# 5-PMU.net
KiCad netlist of a schematic drawn in Altium Designer
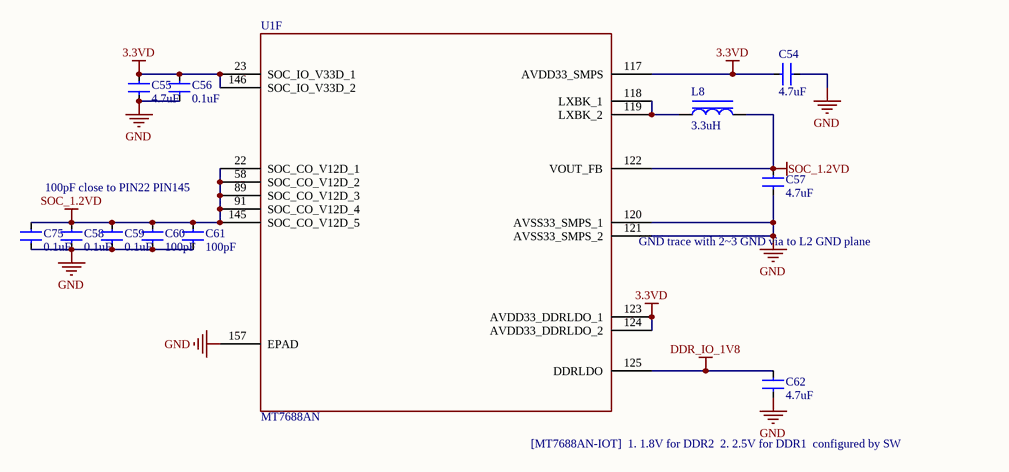
[diagram p0: 5-PMU.SchDoc]

(export (version "E")
  (design (tool "Eeschema 10.0.6"))
  (components
    (comp (ref "C54")
      (value "4.7uF")
      (footprint "C0402")
      (description "普通小电容")
      (libsource (lib "LIB_MANGO") (part "CAP"))
    )
    (comp (ref "C55")
      (value "4.7uF")
      (footprint "C0402")
      (description "普通小电容")
      (libsource (lib "LIB_MANGO") (part "CAP"))
    )
    (comp (ref "C56")
      (value "0.1uF")
      (footprint "C0402")
      (description "普通小电容")
      (libsource (lib "LIB_MANGO") (part "CAP"))
    )
    (comp (ref "C57")
      (value "4.7uF")
      (footprint "C0402")
      (description "普通小电容")
      (libsource (lib "LIB_MANGO") (part "CAP"))
    )
    (comp (ref "C58")
      (value "0.1uF")
      (footprint "C0402")
      (description "普通小电容")
      (libsource (lib "LIB_MANGO") (part "CAP"))
    )
    (comp (ref "C59")
      (value "0.1uF")
      (footprint "C0402")
      (description "普通小电容")
      (libsource (lib "LIB_MANGO") (part "CAP"))
    )
    (comp (ref "C60")
      (value "100pF")
      (footprint "C0402")
      (description "普通小电容")
      (libsource (lib "LIB_MANGO") (part "CAP"))
    )
    (comp (ref "C61")
      (value "100pF")
      (footprint "C0402")
      (description "普通小电容")
      (libsource (lib "LIB_MANGO") (part "CAP"))
    )
    (comp (ref "C62")
      (value "4.7uF")
      (footprint "C0402")
      (description "普通小电容")
      (libsource (lib "LIB_MANGO") (part "CAP"))
    )
    (comp (ref "C75")
      (value "0.1uF")
      (footprint "C0402")
      (description "普通小电容")
      (libsource (lib "LIB_MANGO") (part "CAP"))
    )
    (comp (ref "L8")
      (value "3.3uH")
      (footprint "VLS3012E")
      (description "vls3012小电感")
      (libsource (lib "LIB_MANGO") (part "L"))
    )
    (comp (ref "U1")
      (value "MT7688AN")
      (footprint "MT7628AN/DRQFN156/SMD/P0.5/12X12")
      (libsource (lib "A") (part "MT7688AN"))
    )
  )
  (nets
    (net (code "1") (name "3.3VD") (class "Default")
      (node (ref "C54") (pin "1") (pinfunction "1_1") (pintype "passive"))
      (node (ref "C55") (pin "1") (pinfunction "1_1") (pintype "passive"))
      (node (ref "C56") (pin "1") (pinfunction "1_1") (pintype "passive"))
      (node (ref "U1") (pin "117") (pinfunction "AVDD33_SMPS_117") (pintype "passive"))
      (node (ref "U1") (pin "123") (pinfunction "AVDD33_DDRLDO_1_123") (pintype "passive"))
      (node (ref "U1") (pin "124") (pinfunction "AVDD33_DDRLDO_2_124") (pintype "passive"))
      (node (ref "U1") (pin "146") (pinfunction "SOC_IO_V33D_2_146") (pintype "passive"))
      (node (ref "U1") (pin "23") (pinfunction "SOC_IO_V33D_1_23") (pintype "passive"))
    )
    (net (code "2") (name "DDR_IO_1V8") (class "Default")
      (node (ref "C62") (pin "1") (pinfunction "1_1") (pintype "passive"))
      (node (ref "U1") (pin "125") (pinfunction "DDRLDO_125") (pintype "passive"))
    )
    (net (code "3") (name "GND") (class "Default")
      (node (ref "C54") (pin "2") (pinfunction "2_2") (pintype "passive"))
      (node (ref "C55") (pin "2") (pinfunction "2_2") (pintype "passive"))
      (node (ref "C56") (pin "2") (pinfunction "2_2") (pintype "passive"))
      (node (ref "C57") (pin "2") (pinfunction "2_2") (pintype "passive"))
      (node (ref "C58") (pin "2") (pinfunction "2_2") (pintype "passive"))
      (node (ref "C59") (pin "2") (pinfunction "2_2") (pintype "passive"))
      (node (ref "C60") (pin "1") (pinfunction "1_1") (pintype "passive"))
      (node (ref "C61") (pin "1") (pinfunction "1_1") (pintype "passive"))
      (node (ref "C62") (pin "2") (pinfunction "2_2") (pintype "passive"))
      (node (ref "C75") (pin "2") (pinfunction "2_2") (pintype "passive"))
      (node (ref "U1") (pin "120") (pinfunction "AVSS33_SMPS_1_120") (pintype "passive"))
      (node (ref "U1") (pin "121") (pinfunction "AVSS33_SMPS_2_121") (pintype "passive"))
      (node (ref "U1") (pin "157") (pinfunction "EPAD_157") (pintype "passive"))
    )
    (net (code "4") (name "Net-(U1F-LXBK_1)") (class "Default")
      (node (ref "L8") (pin "2") (pinfunction "2_2") (pintype "passive"))
      (node (ref "U1") (pin "118") (pinfunction "LXBK_1_118") (pintype "passive"))
      (node (ref "U1") (pin "119") (pinfunction "LXBK_2_119") (pintype "passive"))
    )
    (net (code "5") (name "SOC_1.2VD") (class "Default")
      (node (ref "C57") (pin "1") (pinfunction "1_1") (pintype "passive"))
      (node (ref "C58") (pin "1") (pinfunction "1_1") (pintype "passive"))
      (node (ref "C59") (pin "1") (pinfunction "1_1") (pintype "passive"))
      (node (ref "C60") (pin "2") (pinfunction "2_2") (pintype "passive"))
      (node (ref "C61") (pin "2") (pinfunction "2_2") (pintype "passive"))
      (node (ref "C75") (pin "1") (pinfunction "1_1") (pintype "passive"))
      (node (ref "L8") (pin "1") (pinfunction "1_1") (pintype "passive"))
      (node (ref "U1") (pin "122") (pinfunction "VOUT_FB_122") (pintype "passive"))
      (node (ref "U1") (pin "145") (pinfunction "SOC_CO_V12D_5_145") (pintype "passive"))
      (node (ref "U1") (pin "22") (pinfunction "SOC_CO_V12D_1_22") (pintype "passive"))
      (node (ref "U1") (pin "58") (pinfunction "SOC_CO_V12D_2_58") (pintype "passive"))
      (node (ref "U1") (pin "89") (pinfunction "SOC_CO_V12D_3_89") (pintype "passive"))
      (node (ref "U1") (pin "91") (pinfunction "SOC_CO_V12D_4_91") (pintype "passive"))
    )
  )
)
